# Procesor-ESP8266.net
KiCad netlist of a schematic drawn in EAGLE
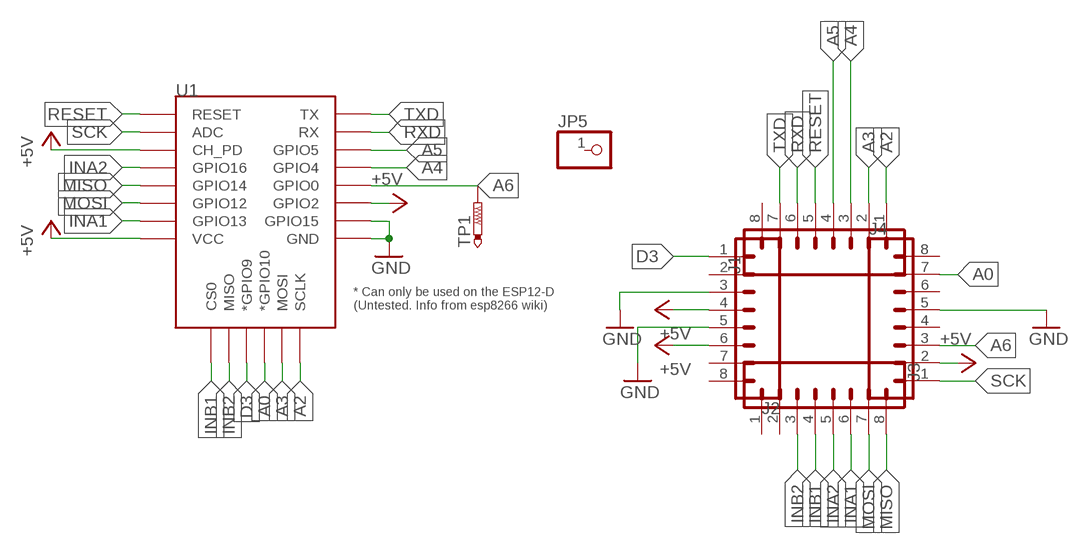
[diagram p0: schematic, sheet 1]

(export (version "E")
  (design (tool "Eeschema 10.0.6"))
  (components
    (comp (ref "J1")
      (value "CONN_08SMD-STRAIGHT-ALT-FEMALE")
      (footprint "eagle-import:1X08_SMD_ALT")
      (libsource (lib "eagle-import") (part "CONN_08SMD-STRAIGHT-ALT-FEMALE"))
    )
    (comp (ref "J2")
      (value "CONN_08SMD-STRAIGHT-ALT-FEMALE")
      (footprint "eagle-import:1X08_SMD_ALT")
      (libsource (lib "eagle-import") (part "CONN_08SMD-STRAIGHT-ALT-FEMALE"))
    )
    (comp (ref "J3")
      (value "CONN_08SMD-STRAIGHT-ALT-FEMALE")
      (footprint "eagle-import:1X08_SMD_ALT")
      (libsource (lib "eagle-import") (part "CONN_08SMD-STRAIGHT-ALT-FEMALE"))
    )
    (comp (ref "J4")
      (value "CONN_08SMD-STRAIGHT-ALT-FEMALE")
      (footprint "eagle-import:1X08_SMD_ALT")
      (libsource (lib "eagle-import") (part "CONN_08SMD-STRAIGHT-ALT-FEMALE"))
    )
    (comp (ref "JP5")
      (value "PINHD-1X1")
      (footprint "eagle-import:1X01")
      (libsource (lib "eagle-import") (part "PINHD-1X1"))
    )
    (comp (ref "TP1")
      (value "PTR1B1,27")
      (footprint "eagle-import:B1,27")
      (libsource (lib "eagle-import") (part "PTR1B1,27"))
    )
    (comp (ref "U1")
      (value "ESP12ESMD")
      (footprint "eagle-import:ESP12E-SMD")
      (libsource (lib "eagle-import") (part "ESP12ESMD"))
    )
  )
  (nets
    (net (code "1") (name "+5V") (class "Default")
      (node (ref "J2") (pin "4") (pinfunction "4_4") (pintype "passive"))
      (node (ref "J2") (pin "6") (pinfunction "6_6") (pintype "passive"))
      (node (ref "J4") (pin "2") (pinfunction "2_2") (pintype "passive"))
      (node (ref "U1") (pin "CH_PD") (pinfunction "CH_PD_CH_PD") (pintype "bidirectional"))
      (node (ref "U1") (pin "GPIO2") (pinfunction "GPIO2_GPIO2") (pintype "bidirectional"))
      (node (ref "U1") (pin "VCC") (pinfunction "VCC_VCC") (pintype "bidirectional"))
    )
    (net (code "2") (name "A0") (class "Default")
      (node (ref "J4") (pin "7") (pinfunction "7_7") (pintype "passive"))
      (node (ref "U1") (pin "GPIO10") (pinfunction "*GPIO10_GPIO10") (pintype "bidirectional"))
    )
    (net (code "3") (name "A2") (class "Default")
      (node (ref "J1") (pin "1") (pinfunction "1_1") (pintype "passive"))
      (node (ref "U1") (pin "SCLK") (pinfunction "SCLK_SCLK") (pintype "bidirectional"))
    )
    (net (code "4") (name "A3") (class "Default")
      (node (ref "J1") (pin "2") (pinfunction "2_2") (pintype "passive"))
      (node (ref "U1") (pin "MOSI") (pinfunction "MOSI_MOSI") (pintype "bidirectional"))
    )
    (net (code "5") (name "A4") (class "Default")
      (node (ref "J1") (pin "3") (pinfunction "3_3") (pintype "passive"))
      (node (ref "U1") (pin "GPIO4") (pinfunction "GPIO4_GPIO4") (pintype "bidirectional"))
    )
    (net (code "6") (name "A5") (class "Default")
      (node (ref "J1") (pin "4") (pinfunction "4_4") (pintype "passive"))
      (node (ref "U1") (pin "GPIO5") (pinfunction "GPIO5_GPIO5") (pintype "bidirectional"))
    )
    (net (code "7") (name "A6") (class "Default")
      (node (ref "J4") (pin "3") (pinfunction "3_3") (pintype "passive"))
      (node (ref "TP1") (pin "TP") (pinfunction "TP_TP") (pintype "input"))
      (node (ref "U1") (pin "GPIO0") (pinfunction "GPIO0_GPIO0") (pintype "bidirectional"))
    )
    (net (code "8") (name "D3") (class "Default")
      (node (ref "J2") (pin "1") (pinfunction "1_1") (pintype "passive"))
      (node (ref "U1") (pin "GPIO9") (pinfunction "*GPIO9_GPIO9") (pintype "bidirectional"))
    )
    (net (code "9") (name "GND") (class "Default")
      (node (ref "J2") (pin "3") (pinfunction "3_3") (pintype "passive"))
      (node (ref "J2") (pin "5") (pinfunction "5_5") (pintype "passive"))
      (node (ref "J4") (pin "5") (pinfunction "5_5") (pintype "passive"))
      (node (ref "U1") (pin "GND") (pinfunction "GND_GND") (pintype "bidirectional"))
      (node (ref "U1") (pin "GPIO15") (pinfunction "GPIO15_GPIO15") (pintype "bidirectional"))
    )
    (net (code "10") (name "INA1") (class "Default")
      (node (ref "J3") (pin "6") (pinfunction "6_6") (pintype "passive"))
      (node (ref "U1") (pin "GPIO13") (pinfunction "GPIO13_GPIO13") (pintype "bidirectional"))
    )
    (net (code "11") (name "INA2") (class "Default")
      (node (ref "J3") (pin "5") (pinfunction "5_5") (pintype "passive"))
      (node (ref "U1") (pin "GPIO16") (pinfunction "GPIO16_GPIO16") (pintype "bidirectional"))
    )
    (net (code "12") (name "INB1") (class "Default")
      (node (ref "J3") (pin "4") (pinfunction "4_4") (pintype "passive"))
      (node (ref "U1") (pin "CS0") (pinfunction "CS0_CS0") (pintype "bidirectional"))
    )
    (net (code "13") (name "INB2") (class "Default")
      (node (ref "J3") (pin "3") (pinfunction "3_3") (pintype "passive"))
      (node (ref "U1") (pin "MISO") (pinfunction "MISO_MISO") (pintype "bidirectional"))
    )
    (net (code "14") (name "MISO") (class "Default")
      (node (ref "J3") (pin "8") (pinfunction "8_8") (pintype "passive"))
      (node (ref "U1") (pin "GPIO14") (pinfunction "GPIO14_GPIO14") (pintype "bidirectional"))
    )
    (net (code "15") (name "MOSI") (class "Default")
      (node (ref "J3") (pin "7") (pinfunction "7_7") (pintype "passive"))
      (node (ref "U1") (pin "GPIO12") (pinfunction "GPIO12_GPIO12") (pintype "bidirectional"))
    )
    (net (code "16") (name "RESET") (class "Default")
      (node (ref "J1") (pin "5") (pinfunction "5_5") (pintype "passive"))
      (node (ref "U1") (pin "RESET") (pinfunction "RESET_RESET") (pintype "bidirectional"))
    )
    (net (code "17") (name "RXD") (class "Default")
      (node (ref "J1") (pin "6") (pinfunction "6_6") (pintype "passive"))
      (node (ref "U1") (pin "RXD0") (pinfunction "RX_RXD0") (pintype "bidirectional"))
    )
    (net (code "18") (name "SCK") (class "Default")
      (node (ref "J4") (pin "1") (pinfunction "1_1") (pintype "passive"))
      (node (ref "U1") (pin "ADC") (pinfunction "ADC_ADC") (pintype "bidirectional"))
    )
    (net (code "19") (name "TXD") (class "Default")
      (node (ref "J1") (pin "7") (pinfunction "7_7") (pintype "passive"))
      (node (ref "U1") (pin "TXD0") (pinfunction "TX_TXD0") (pintype "bidirectional"))
    )
    (net (code "20") (name "unconnected-(J1-Pad8)") (class "Default")
      (node (ref "J1") (pin "8") (pinfunction "8_8") (pintype "passive"))
    )
    (net (code "21") (name "unconnected-(J2-Pad2)") (class "Default")
      (node (ref "J2") (pin "2") (pinfunction "2_2") (pintype "passive"))
    )
    (net (code "22") (name "unconnected-(J2-Pad7)") (class "Default")
      (node (ref "J2") (pin "7") (pinfunction "7_7") (pintype "passive"))
    )
    (net (code "23") (name "unconnected-(J2-Pad8)") (class "Default")
      (node (ref "J2") (pin "8") (pinfunction "8_8") (pintype "passive"))
    )
    (net (code "24") (name "unconnected-(J3-Pad1)") (class "Default")
      (node (ref "J3") (pin "1") (pinfunction "1_1") (pintype "passive"))
    )
    (net (code "25") (name "unconnected-(J3-Pad2)") (class "Default")
      (node (ref "J3") (pin "2") (pinfunction "2_2") (pintype "passive"))
    )
    (net (code "26") (name "unconnected-(J4-Pad4)") (class "Default")
      (node (ref "J4") (pin "4") (pinfunction "4_4") (pintype "passive"))
    )
    (net (code "27") (name "unconnected-(J4-Pad6)") (class "Default")
      (node (ref "J4") (pin "6") (pinfunction "6_6") (pintype "passive"))
    )
    (net (code "28") (name "unconnected-(J4-Pad8)") (class "Default")
      (node (ref "J4") (pin "8") (pinfunction "8_8") (pintype "passive"))
    )
    (net (code "29") (name "unconnected-(JP5-Pad1)") (class "Default")
      (node (ref "JP5") (pin "1") (pinfunction "1_1") (pintype "passive"))
    )
  )
)
